# BLOCK_DETAIL.net
KiCad netlist of a schematic drawn in Altium Designer
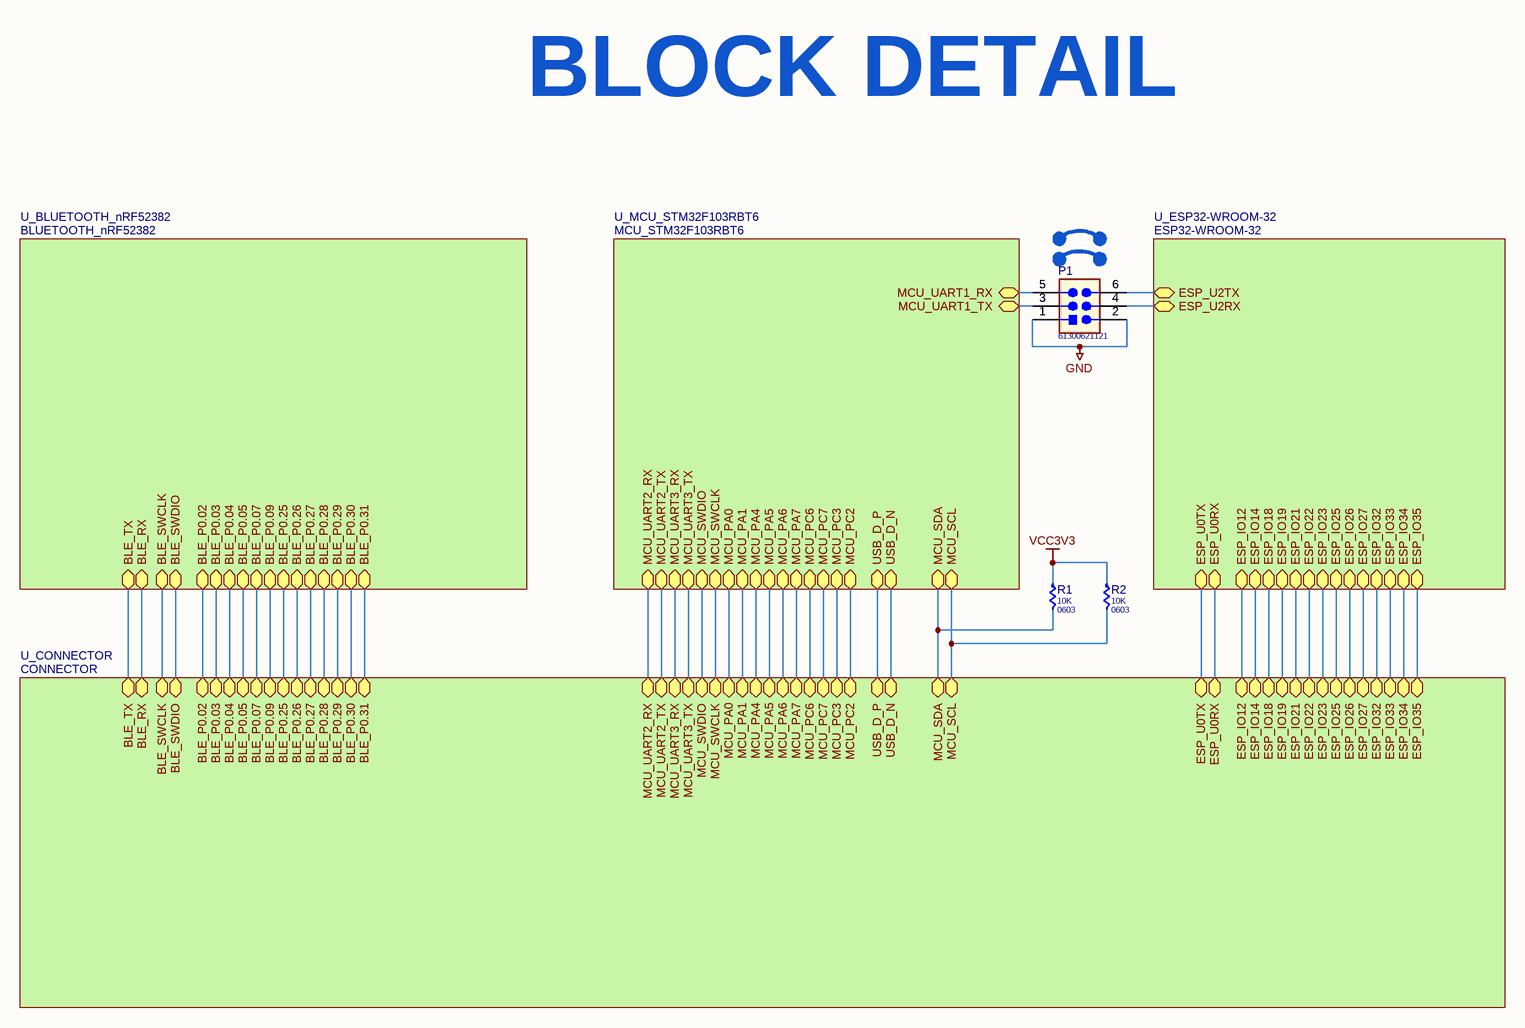
[diagram p0: BLOCK_DETAIL.SchDoc]

(export (version "E")
  (design (tool "Eeschema 10.0.6"))
  (components
    (comp (ref "P1")
      (value "61300621121")
      (footprint "CON_6_2.54P")
      (description "CON C2B 2R8C M 2.54P THR")
      (fields (field (name "MGR PN") "61300621121"))
      (libsource (lib "FENIKAA_LIB") (part "CON_2x3"))
    )
    (comp (ref "R1")
      (value "10K")
      (footprint "R0603")
      (description "RES CHP 10K 1% 1/10W 0603 SMD")
      (fields (field (name "POWER") "1/10W") (field (name "PACK") "0603") (field (name "TOLERANCE") "1%"))
      (libsource (lib "FENIKAA_LIB") (part "R0603_10K_1/10W_1%"))
    )
    (comp (ref "R2")
      (value "10K")
      (footprint "R0603")
      (description "RES CHP 10K 1% 1/10W 0603 SMD")
      (fields (field (name "POWER") "1/10W") (field (name "PACK") "0603") (field (name "TOLERANCE") "1%"))
      (libsource (lib "FENIKAA_LIB") (part "R0603_10K_1/10W_1%"))
    )
  )
  (nets
    (net (code "34") (name "/ESP_U2RX") (class "Default")
      (node (ref "P1") (pin "4") (pinfunction "4_4") (pintype "passive"))
    )
    (net (code "35") (name "/ESP_U2TX") (class "Default")
      (node (ref "P1") (pin "6") (pinfunction "6_6") (pintype "passive"))
    )
    (net (code "46") (name "/MCU_SCL") (class "Default")
      (node (ref "R2") (pin "2") (pinfunction "2_2") (pintype "passive"))
    )
    (net (code "47") (name "/MCU_SDA") (class "Default")
      (node (ref "R1") (pin "2") (pinfunction "2_2") (pintype "passive"))
    )
    (net (code "50") (name "/MCU_UART1_RX") (class "Default")
      (node (ref "P1") (pin "5") (pinfunction "5_5") (pintype "passive"))
    )
    (net (code "51") (name "/MCU_UART1_TX") (class "Default")
      (node (ref "P1") (pin "3") (pinfunction "3_3") (pintype "passive"))
    )
    (net (code "58") (name "GND") (class "Default")
      (node (ref "P1") (pin "1") (pinfunction "1_1") (pintype "passive"))
      (node (ref "P1") (pin "2") (pinfunction "2_2") (pintype "passive"))
    )
    (net (code "59") (name "VCC3V3") (class "Default")
      (node (ref "R1") (pin "1") (pinfunction "1_1") (pintype "passive"))
      (node (ref "R2") (pin "1") (pinfunction "1_1") (pintype "passive"))
    )
  )
)
